# SUPPLY.net
KiCad netlist of a schematic drawn in Altium Designer
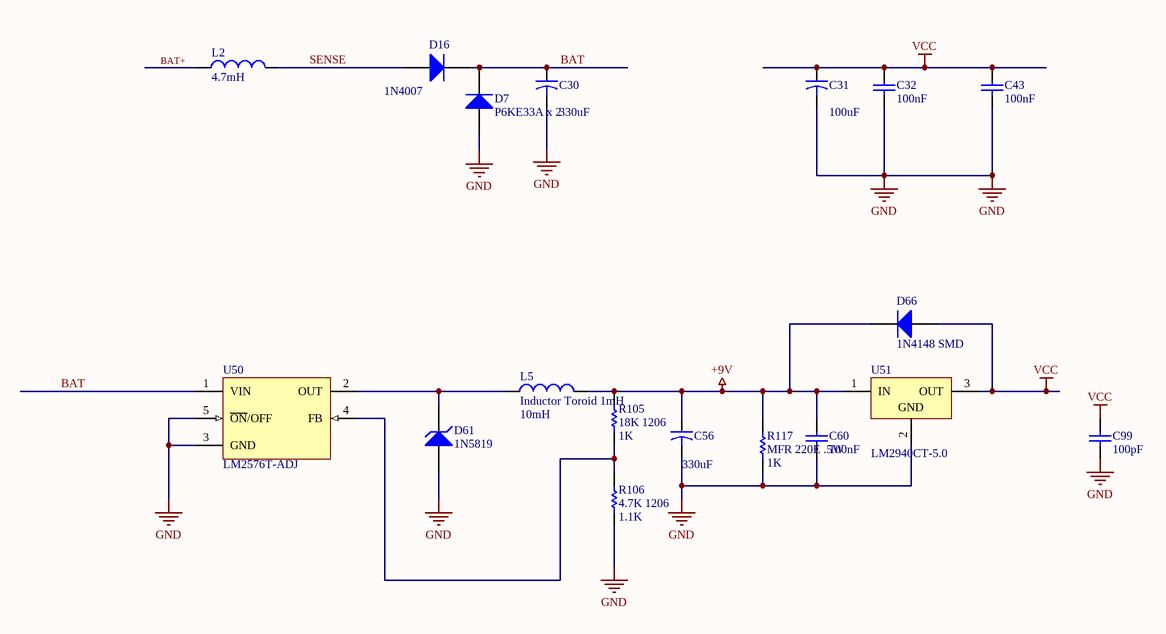
[diagram p0: SUPPLY.SchDoc]

(export (version "E")
  (design (tool "Eeschema 10.0.6"))
  (components
    (comp (ref "C30")
      (value "330uF")
      (footprint "Cap_.2-2")
      (description "Capacitor")
      (fields
        (field (name "Comment") "Cap Electrolitic 1000uF/50V")
        (field (name "PUBLISHER") "Altium Limited")
      )
      (libsource (lib "Miscellaneous Devices") (part "Cap2"))
    )
    (comp (ref "C31")
      (value "100uF")
      (footprint "Cap_.2")
      (description "Capacitor")
      (fields
        (field (name "Comment") "Cap Electrolytic 470uF/16V")
        (field (name "PUBLISHER") "Altium Limited")
      )
      (libsource (lib "Miscellaneous Devices") (part "Cap2"))
    )
    (comp (ref "C32")
      (value "100nF")
      (footprint "C1206VW")
      (description "Capacitor")
      (fields (field (name "Comment") ".1uF 1206") (field (name "PUBLISHER") "Altium Limited"))
      (libsource (lib "Miscellaneous Devices") (part "Cap"))
    )
    (comp (ref "C43")
      (value "100nF")
      (footprint "C1206VW")
      (description "Capacitor")
      (fields (field (name "Comment") "1uF 1206") (field (name "PUBLISHER") "Altium Limited"))
      (libsource (lib "Miscellaneous Devices") (part "Cap"))
    )
    (comp (ref "C56")
      (value "330uF")
      (footprint "Cap_.3")
      (description "Capacitor")
      (fields
        (field (name "Comment") "Cap Electrolitic 3300uF/16V")
        (field (name "PUBLISHER") "Altium Limited")
      )
      (libsource (lib "Miscellaneous Devices") (part "Cap2"))
    )
    (comp (ref "C60")
      (value "100nF")
      (footprint "C1206VW")
      (description "Capacitor")
      (fields (field (name "Comment") ".1uF 1206") (field (name "PUBLISHER") "Altium Limited"))
      (libsource (lib "Miscellaneous Devices") (part "Cap"))
    )
    (comp (ref "C99")
      (value "100pF")
      (footprint "C1206VW")
      (description "Capacitor")
      (fields (field (name "Comment") ".1uF 1206") (field (name "PUBLISHER") "Altium Limited"))
      (libsource (lib "Miscellaneous Devices") (part "Cap"))
    )
    (comp (ref "D7")
      (value "P6KE33A x 2")
      (footprint "DIODE1A")
      (description "3 Amp Medium Power Silicon Rectifier Diode")
      (fields (field (name "PUBLISHER") "Altium Limited"))
      (libsource (lib "Miscellaneous Devices") (part "Diode 1N5408"))
    )
    (comp (ref "D16")
      (value "1N4007")
      (footprint "DIODE1A")
      (description "3 Amp Medium Power Silicon Rectifier Diode")
      (fields (field (name "PUBLISHER") "Altium Limited"))
      (libsource (lib "Miscellaneous Devices") (part "Diode 1N5408"))
    )
    (comp (ref "D61")
      (value "1N5819")
      (footprint "DIODE1A")
      (description "Silicon Zener Diode (0.3 to 0.5W)")
      (fields (field (name "PUBLISHER") "Altium Limited"))
      (libsource (lib "Vishay Telefunken Discrete Diode") (part "1N5221B"))
    )
    (comp (ref "D66")
      (value "1N4148 SMD")
      (footprint "4148SMD")
      (description "Small Signal Fast Switching Diode")
      (fields (field (name "PUBLISHER") "Altium Limited"))
      (libsource (lib "Miscellaneous Devices") (part "Diode 1N5408"))
    )
    (comp (ref "L2")
      (value "4.7mH")
      (footprint "INDUCTOR")
      (description "Inductor")
      (fields (field (name "Comment") "Inductor 220uH") (field (name "PUBLISHER") "Altium Limited"))
      (libsource (lib "Miscellaneous Devices") (part "Inductor"))
    )
    (comp (ref "L5")
      (value "Inductor Toroid 1mH")
      (footprint "INDUCTORTOROID")
      (description "Inductor")
      (fields (field (name "ALTIUM_VALUE") "10mH") (field (name "PUBLISHER") "Altium Limited"))
      (libsource (lib "Miscellaneous Devices") (part "Inductor"))
    )
    (comp (ref "R105")
      (value "18K 1206")
      (footprint "R1206VW")
      (description "Semiconductor Resistor")
      (fields (field (name "ALTIUM_VALUE") "1K") (field (name "PUBLISHER") "Altium Limited"))
      (libsource (lib "PCB_Project1") (part "Res SMT"))
    )
    (comp (ref "R106")
      (value "4.7K 1206")
      (footprint "R1206VW")
      (description "Semiconductor Resistor")
      (fields (field (name "ALTIUM_VALUE") "1.1K") (field (name "PUBLISHER") "Altium Limited"))
      (libsource (lib "PCB_Project1") (part "Res SMT"))
    )
    (comp (ref "R117")
      (value "MFR 220E .5W")
      (footprint "AXIAL-0.5")
      (description "Semiconductor Resistor")
      (fields (field (name "ALTIUM_VALUE") "1K") (field (name "PUBLISHER") "Altium Limited"))
      (libsource (lib "Miscellaneous Devices") (part "Res Semi"))
    )
    (comp (ref "U50")
      (value "LM2576T-ADJ")
      (footprint "T05D")
      (description "SIMPLE SWITCHER® 3A Step-Down Voltage Regulator, 5-pin TO-220")
      (fields
        (field (name "MANUFACTURER") "National Semiconductor")
        (field (name "PUBLISHER") "Altium Limited")
      )
      (libsource (lib "NSC Switcher") (part "LM2576T-ADJ"))
    )
    (comp (ref "U51")
      (value "LM2940CT-5.0")
      (footprint "T03B")
      (description "1A Low Dropout Regulator, 3-pin TO-220")
      (fields
        (field (name "MANUFACTURER") "National Semiconductor")
        (field (name "PUBLISHER") "Altium Limited")
      )
      (libsource (lib "NSC LDO") (part "LM2940CT-5.0"))
    )
  )
  (nets
    (net (code "1") (name "+9V") (class "Default")
      (node (ref "C56") (pin "1") (pinfunction "1_1") (pintype "passive"))
      (node (ref "C60") (pin "2") (pinfunction "2_2") (pintype "passive"))
      (node (ref "D66") (pin "2") (pinfunction "K_2") (pintype "passive"))
      (node (ref "L5") (pin "2") (pinfunction "2_2") (pintype "passive"))
      (node (ref "R105") (pin "2") (pinfunction "2_2") (pintype "passive"))
      (node (ref "R117") (pin "2") (pinfunction "2_2") (pintype "passive"))
      (node (ref "U51") (pin "1") (pinfunction "IN_1") (pintype "power_in"))
    )
    (net (code "2") (name "/BAT") (class "Default")
      (node (ref "C30") (pin "1") (pinfunction "1_1") (pintype "passive"))
      (node (ref "D16") (pin "2") (pinfunction "K_2") (pintype "passive"))
      (node (ref "D7") (pin "2") (pinfunction "K_2") (pintype "passive"))
      (node (ref "U50") (pin "1") (pinfunction "VIN_1") (pintype "power_in"))
    )
    (net (code "3") (name "/BAT+") (class "Default")
      (node (ref "L2") (pin "1") (pinfunction "1_1") (pintype "passive"))
    )
    (net (code "4") (name "/SENSE") (class "Default")
      (node (ref "D16") (pin "1") (pinfunction "A_1") (pintype "passive"))
      (node (ref "L2") (pin "2") (pinfunction "2_2") (pintype "passive"))
    )
    (net (code "5") (name "GND") (class "Default")
      (node (ref "C30") (pin "2") (pinfunction "2_2") (pintype "passive"))
      (node (ref "C31") (pin "2") (pinfunction "2_2") (pintype "passive"))
      (node (ref "C32") (pin "1") (pinfunction "1_1") (pintype "passive"))
      (node (ref "C43") (pin "1") (pinfunction "1_1") (pintype "passive"))
      (node (ref "C56") (pin "2") (pinfunction "2_2") (pintype "passive"))
      (node (ref "C60") (pin "1") (pinfunction "1_1") (pintype "passive"))
      (node (ref "C99") (pin "1") (pinfunction "1_1") (pintype "passive"))
      (node (ref "D61") (pin "1") (pinfunction "A_1") (pintype "passive"))
      (node (ref "D7") (pin "1") (pinfunction "A_1") (pintype "passive"))
      (node (ref "R106") (pin "1") (pinfunction "1_1") (pintype "passive"))
      (node (ref "R117") (pin "1") (pinfunction "1_1") (pintype "passive"))
      (node (ref "U50") (pin "3") (pinfunction "GND_3") (pintype "power_in"))
      (node (ref "U50") (pin "5") (pinfunction "~{ON}/OFF_5") (pintype "input"))
      (node (ref "U51") (pin "2") (pinfunction "GND_2") (pintype "power_in"))
    )
    (net (code "6") (name "Net-(D61-K)") (class "Default")
      (node (ref "D61") (pin "2") (pinfunction "K_2") (pintype "passive"))
      (node (ref "L5") (pin "1") (pinfunction "1_1") (pintype "passive"))
      (node (ref "U50") (pin "2") (pinfunction "OUT_2") (pintype "power_in"))
    )
    (net (code "7") (name "Net-(U50-FB)") (class "Default")
      (node (ref "R105") (pin "1") (pinfunction "1_1") (pintype "passive"))
      (node (ref "R106") (pin "2") (pinfunction "2_2") (pintype "passive"))
      (node (ref "U50") (pin "4") (pinfunction "FB_4") (pintype "input"))
    )
    (net (code "8") (name "VCC") (class "Default")
      (node (ref "C31") (pin "1") (pinfunction "1_1") (pintype "passive"))
      (node (ref "C32") (pin "2") (pinfunction "2_2") (pintype "passive"))
      (node (ref "C43") (pin "2") (pinfunction "2_2") (pintype "passive"))
      (node (ref "C99") (pin "2") (pinfunction "2_2") (pintype "passive"))
      (node (ref "D66") (pin "1") (pinfunction "A_1") (pintype "passive"))
      (node (ref "U51") (pin "3") (pinfunction "OUT_3") (pintype "power_in"))
    )
  )
)
